# Count_3x7Seg_Display.net
KiCad netlist of a schematic drawn in Altium Designer
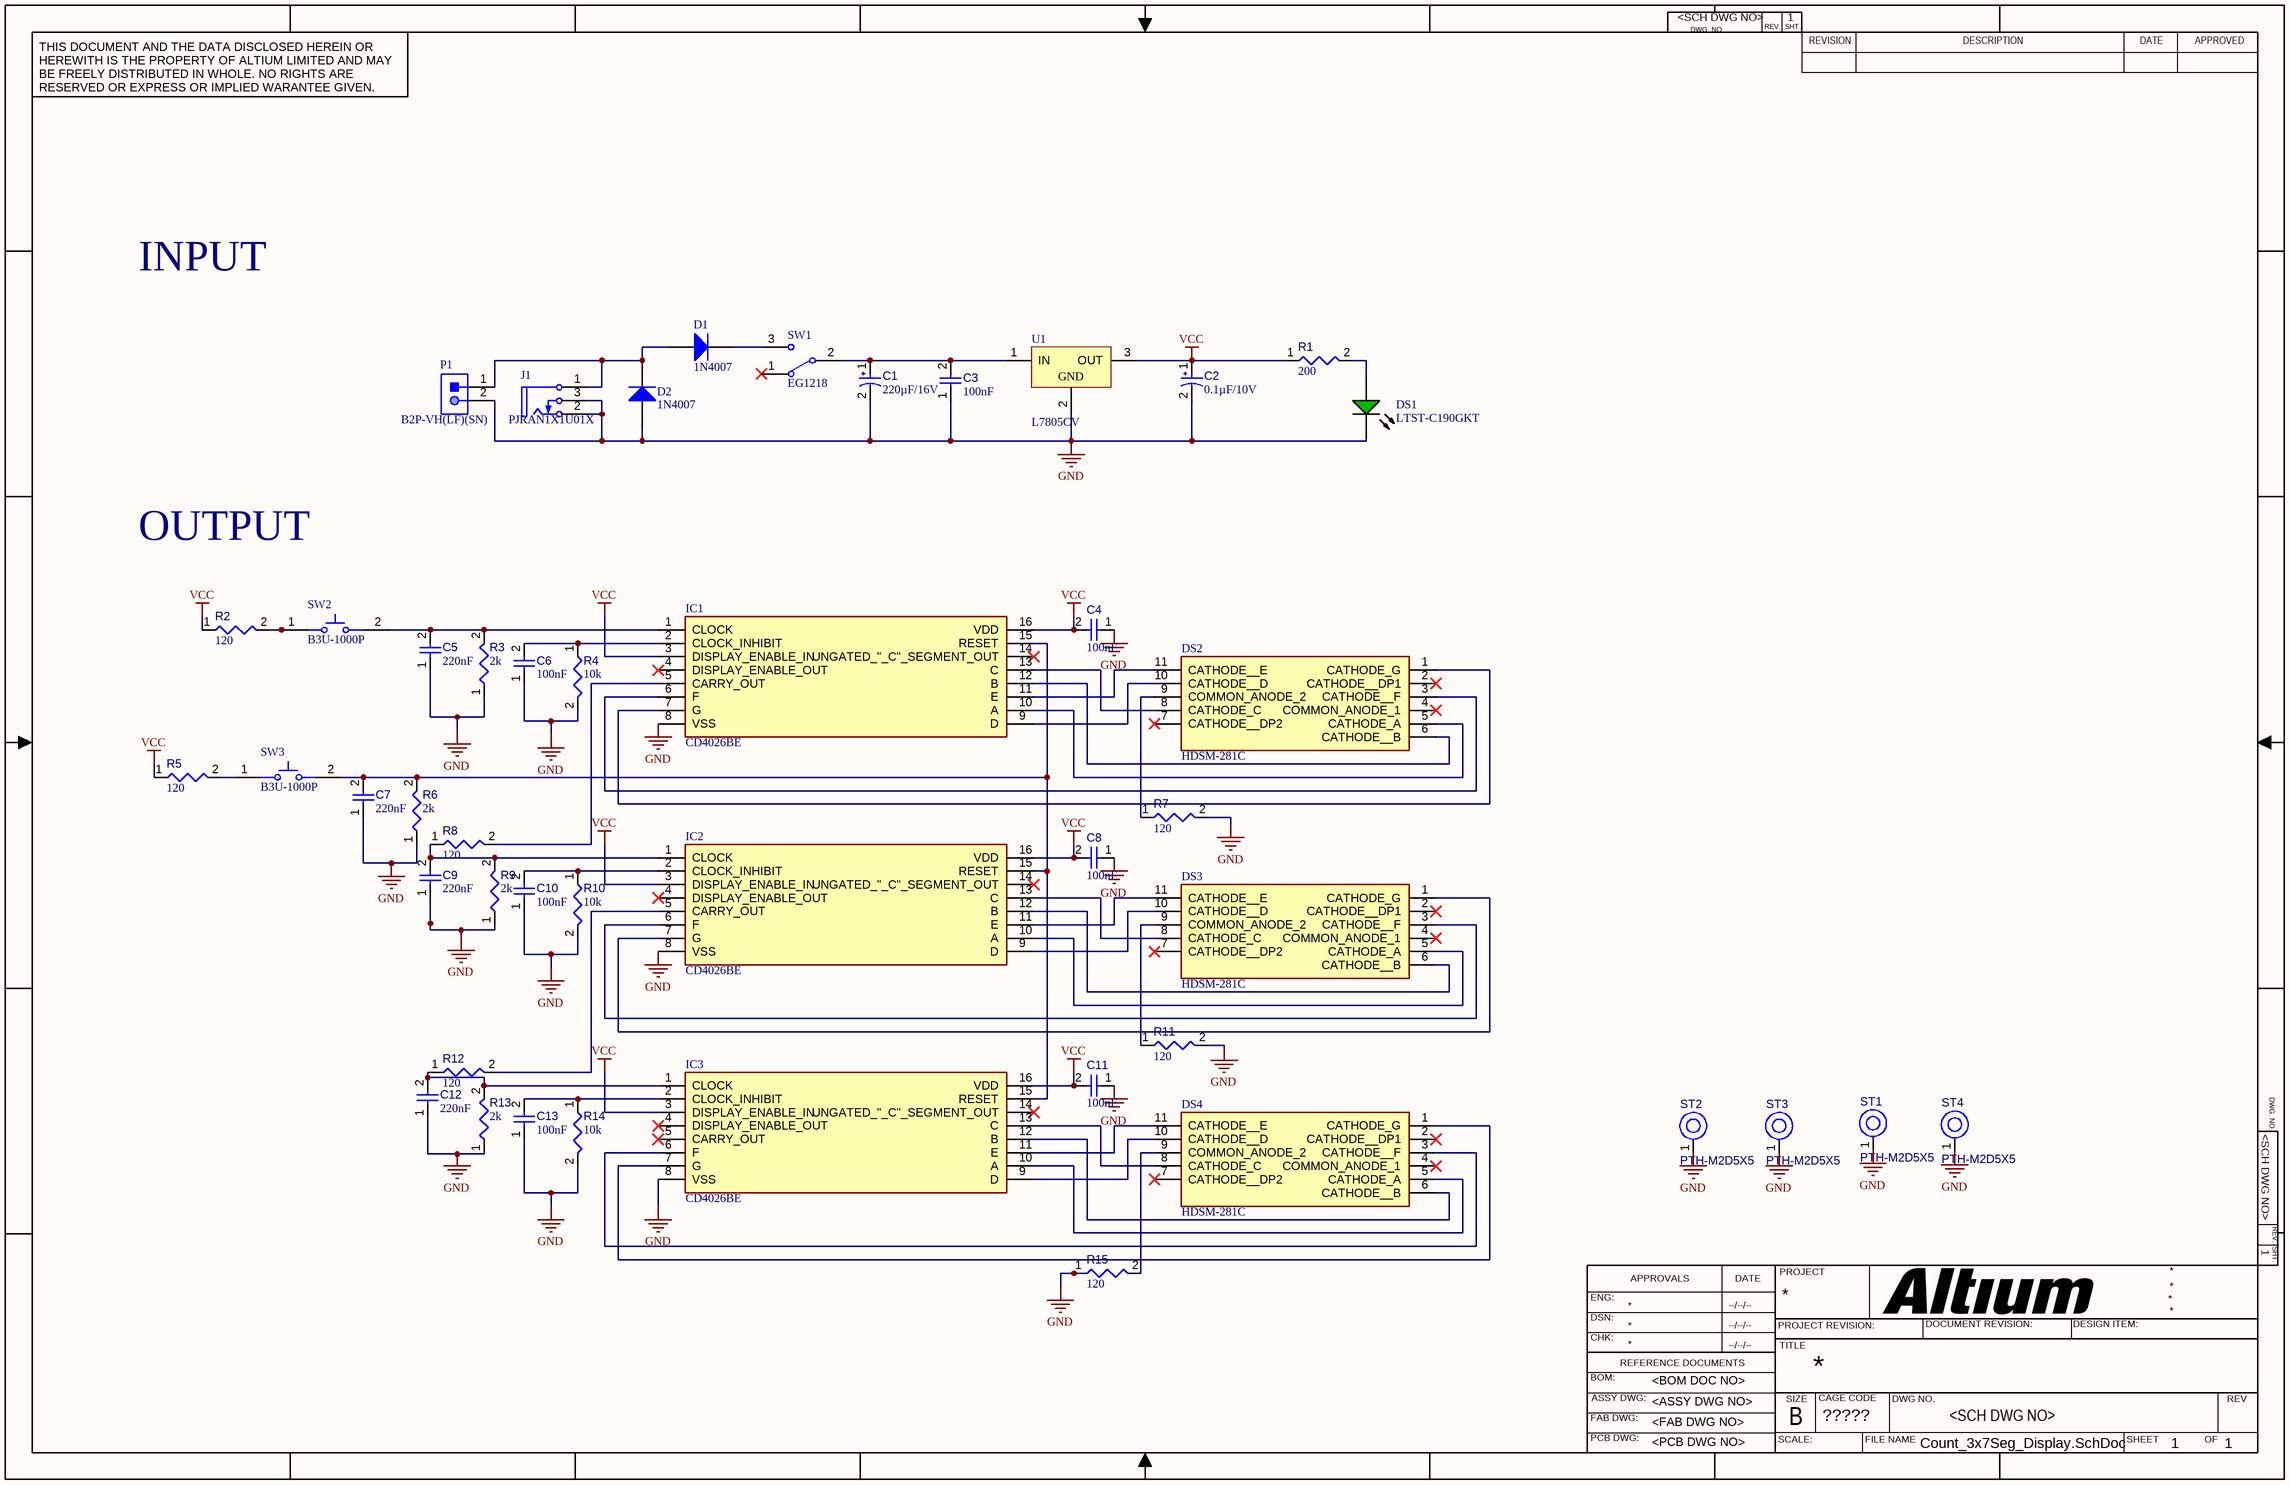
[diagram p0: Count_3x7Seg_Display.SchDoc]

(export (version "E")
  (design (tool "Eeschema 10.0.6"))
  (components
    (comp (ref "C1")
      (value "220µF/16V")
      (footprint "CAPPR55-250-1120X630X1220")
      (description "Aluminum Electrolytic Capacitor, 47 uF, +/-20%, 50 V, -40 to 85 degC, 2-Pin THD, RoHS, Bulk")
      (fields (field (name "TOLERANCE") "20%") (field (name "MANUFACTURER") "Panasonic"))
      (libsource (lib "Paris - Saclay University") (part "CAP-P-2"))
    )
    (comp (ref "C2")
      (value "0.1µF/10V")
      (footprint "CAPPR55-250-1120X630X1220")
      (description "Aluminum Electrolytic Capacitor, 47 uF, +/-20%, 50 V, -40 to 85 degC, 2-Pin THD, RoHS, Bulk")
      (fields (field (name "TOLERANCE") "20%") (field (name "MANUFACTURER") "Panasonic"))
      (libsource (lib "Paris - Saclay University") (part "CAP-P-2"))
    )
    (comp (ref "C3")
      (value "100nF")
      (footprint "CAPC1608X90X40NL10T20")
      (description "Chip Capacitor, 100 nF, +/- 10%, 50 V, 0603 (1608 Metric)")
      (fields (field (name "TOLERANCE") "10%") (field (name "Comment") "Capacitor 100 nF +/-10% 50 V 0603"))
      (libsource (lib "Paris - Saclay University") (part "CAP-NP-2"))
    )
    (comp (ref "C4")
      (value "100nF")
      (footprint "CAPC1608X90X40NL10T20")
      (description "Chip Capacitor, 100 nF, +/- 10%, 50 V, 0603 (1608 Metric)")
      (fields (field (name "TOLERANCE") "10%") (field (name "Comment") "Capacitor 100 nF +/-10% 50 V 0603"))
      (libsource (lib "Paris - Saclay University") (part "CAP-NP-2"))
    )
    (comp (ref "C5")
      (value "220nF")
      (footprint "CAPC0402(1005)60_L")
      (description "Chip Capacitor, 220nF +/-20%, 10V, 0402, Thickness 0.6 mm")
      (fields (field (name "TOLERANCE") "10%") (field (name "Comment") "Capacitor 220nF +/-20% 10V 0402"))
      (libsource (lib "Paris - Saclay University") (part "CAP-NP-2"))
    )
    (comp (ref "C6")
      (value "100nF")
      (footprint "CAPC1608X90X40NL10T20")
      (description "Chip Capacitor, 100 nF, +/- 10%, 50 V, 0603 (1608 Metric)")
      (fields (field (name "TOLERANCE") "10%") (field (name "Comment") "Capacitor 100 nF +/-10% 50 V 0603"))
      (libsource (lib "Paris - Saclay University") (part "CAP-NP-2"))
    )
    (comp (ref "C7")
      (value "220nF")
      (footprint "CAPC0402(1005)60_L")
      (description "Chip Capacitor, 220nF +/-20%, 10V, 0402, Thickness 0.6 mm")
      (fields (field (name "TOLERANCE") "10%") (field (name "Comment") "Capacitor 220nF +/-20% 10V 0402"))
      (libsource (lib "Paris - Saclay University") (part "CAP-NP-2"))
    )
    (comp (ref "C8")
      (value "100nF")
      (footprint "CAPC1608X90X40NL10T20")
      (description "Chip Capacitor, 100 nF, +/- 10%, 50 V, 0603 (1608 Metric)")
      (fields (field (name "TOLERANCE") "10%") (field (name "Comment") "Capacitor 100 nF +/-10% 50 V 0603"))
      (libsource (lib "Paris - Saclay University") (part "CAP-NP-2"))
    )
    (comp (ref "C9")
      (value "220nF")
      (footprint "CAPC0402(1005)60_L")
      (description "Chip Capacitor, 220nF +/-20%, 10V, 0402, Thickness 0.6 mm")
      (fields (field (name "TOLERANCE") "10%") (field (name "Comment") "Capacitor 220nF +/-20% 10V 0402"))
      (libsource (lib "Paris - Saclay University") (part "CAP-NP-2"))
    )
    (comp (ref "C10")
      (value "100nF")
      (footprint "CAPC1608X90X40NL10T20")
      (description "Chip Capacitor, 100 nF, +/- 10%, 50 V, 0603 (1608 Metric)")
      (fields (field (name "TOLERANCE") "10%") (field (name "Comment") "Capacitor 100 nF +/-10% 50 V 0603"))
      (libsource (lib "Paris - Saclay University") (part "CAP-NP-2"))
    )
    (comp (ref "C11")
      (value "100nF")
      (footprint "CAPC1608X90X40NL10T20")
      (description "Chip Capacitor, 100 nF, +/- 10%, 50 V, 0603 (1608 Metric)")
      (fields (field (name "TOLERANCE") "10%") (field (name "Comment") "Capacitor 100 nF +/-10% 50 V 0603"))
      (libsource (lib "Paris - Saclay University") (part "CAP-NP-2"))
    )
    (comp (ref "C12")
      (value "220nF")
      (footprint "CAPC0402(1005)60_L")
      (description "Chip Capacitor, 220nF +/-20%, 10V, 0402, Thickness 0.6 mm")
      (fields (field (name "TOLERANCE") "10%") (field (name "Comment") "Capacitor 220nF +/-20% 10V 0402"))
      (libsource (lib "Paris - Saclay University") (part "CAP-NP-2"))
    )
    (comp (ref "C13")
      (value "100nF")
      (footprint "CAPC1608X90X40NL10T20")
      (description "Chip Capacitor, 100 nF, +/- 10%, 50 V, 0603 (1608 Metric)")
      (fields (field (name "TOLERANCE") "10%") (field (name "Comment") "Capacitor 100 nF +/-10% 50 V 0603"))
      (libsource (lib "Paris - Saclay University") (part "CAP-NP-2"))
    )
    (comp (ref "D1")
      (value "1N4007")
      (footprint "FAIR-DO-41-2")
      (description "General Purpose Rectifier, 1.1 V, 1.0 A, -55 to 175 degC, 2-Pin DO-41, RoHS, Tape and Reel")
      (fields (field (name "MANUFACTURER") "Fairchild"))
      (libsource (lib "Paris - Saclay University") (part "KESE-D_K1A2-2"))
    )
    (comp (ref "D2")
      (value "1N4007")
      (footprint "FAIR-DO-41-2")
      (description "General Purpose Rectifier, 1.1 V, 1.0 A, -55 to 175 degC, 2-Pin DO-41, RoHS, Tape and Reel")
      (fields (field (name "MANUFACTURER") "Fairchild"))
      (libsource (lib "Paris - Saclay University") (part "KESE-D_K1A2-2"))
    )
    (comp (ref "DS1")
      (value "LTST-C190GKT")
      (footprint "LTST-C190GKT_V")
      (description "LED Uni-Color Green, 100 mW, 30 mA, -55 to 85 degC, 2-Pin SMD, RoHS, Tape and Reel")
      (fields (field (name "POWER") "100mW") (field (name "MANUFACTURER") "Lite-On"))
      (libsource (lib "Paris - Saclay University") (part "LED-GREEN-AK-2"))
    )
    (comp (ref "DS2")
      (value "HDSM-281C")
      (footprint "SamacSys:HDSM283L")
      (description "Display")
      (fields (field (name "MOUSER PART NUMBER") "630-HDSM-281C"))
      (libsource (lib "*") (part "HDSM-281C"))
    )
    (comp (ref "DS3")
      (value "HDSM-281C")
      (footprint "SamacSys:HDSM283L")
      (description "Display")
      (fields (field (name "MOUSER PART NUMBER") "630-HDSM-281C"))
      (libsource (lib "*") (part "HDSM-281C"))
    )
    (comp (ref "DS4")
      (value "HDSM-281C")
      (footprint "SamacSys:HDSM283L")
      (description "Display")
      (fields (field (name "MOUSER PART NUMBER") "630-HDSM-281C"))
      (libsource (lib "*") (part "HDSM-281C"))
    )
    (comp (ref "IC1")
      (value "CD4026BE")
      (footprint "SamacSys:DIP794W53P254L1930H508Q16N")
      (description "Integrated Circuit")
      (fields (field (name "MOUSER PART NUMBER") "595-CD4026BE"))
      (libsource (lib "*") (part "CD4026BE"))
    )
    (comp (ref "IC2")
      (value "CD4026BE")
      (footprint "SamacSys:DIP794W53P254L1930H508Q16N")
      (description "Integrated Circuit")
      (fields (field (name "MOUSER PART NUMBER") "595-CD4026BE"))
      (libsource (lib "*") (part "CD4026BE"))
    )
    (comp (ref "IC3")
      (value "CD4026BE")
      (footprint "SamacSys:DIP794W53P254L1930H508Q16N")
      (description "Integrated Circuit")
      (fields (field (name "MOUSER PART NUMBER") "595-CD4026BE"))
      (libsource (lib "*") (part "CD4026BE"))
    )
    (comp (ref "J1")
      (value "PJRAN1X1U01X")
      (footprint "SWIT-PJRAN1X1U01X_V")
      (description "Female Phono Jack, 3 Position, Height 13 mm, Tail Length 4 mm, RoHS, Bulk")
      (fields (field (name "MANUFACTURER") "Switchcraft"))
      (libsource (lib "Paris - Saclay University") (part "JACK-2CD3-TN"))
    )
    (comp (ref "P1")
      (value "B2P-VH(LF)(SN)")
      (footprint "JST-B2P-VH(LF)(SN)_V")
      (fields (field (name "MANUFACTURER") "JST"))
      (libsource (lib "Paris - Saclay University") (part "CN-1P-M-R2"))
    )
    (comp (ref "R1")
      (value "200")
      (footprint "RESC0402(1005)_L")
      (description "200R 0.063W 5% 0402 (1005 Metric)  SMD")
      (fields (field (name "TOLERANCE") "5%") (field (name "POWER") "63mW"))
      (libsource (lib "Paris - Saclay University") (part "200R2J"))
    )
    (comp (ref "R2")
      (value "120")
      (footprint "RESC0603(1608)_L")
      (description "120R 0.1W 5% 0603 (1608 Metric)  SMD")
      (fields (field (name "POWER") "100mW") (field (name "TOLERANCE") "5%"))
      (libsource (lib "Paris - Saclay University") (part "120R3J"))
    )
    (comp (ref "R3")
      (value "2k")
      (footprint "RESC0402(1005)_L")
      (description "Chip Resistor, 2 kOhms, +/-5 %, 63 mW, -55 to 155 degC, 0402")
      (fields (field (name "TOLERANCE") "5%") (field (name "POWER") "63mW"))
      (libsource (lib "Paris - Saclay University") (part "RES-2"))
    )
    (comp (ref "R4")
      (value "10k")
      (footprint "RESC1005X40X25ML05T05")
      (description "Chip Resistor, 10 KOhm, +/- 1%, 0.1 W, -55 to 155 degC, 0402 (1005 Metric)")
      (fields (field (name "TOLERANCE") "1%") (field (name "POWER") "100mW"))
      (libsource (lib "Paris - Saclay University") (part "RES-2"))
    )
    (comp (ref "R5")
      (value "120")
      (footprint "RESC0603(1608)_L")
      (description "120R 0.1W 5% 0603 (1608 Metric)  SMD")
      (fields (field (name "POWER") "100mW") (field (name "TOLERANCE") "5%"))
      (libsource (lib "Paris - Saclay University") (part "120R3J"))
    )
    (comp (ref "R6")
      (value "2k")
      (footprint "RESC0402(1005)_L")
      (description "Chip Resistor, 2 kOhms, +/-5 %, 63 mW, -55 to 155 degC, 0402")
      (fields (field (name "TOLERANCE") "5%") (field (name "POWER") "63mW"))
      (libsource (lib "Paris - Saclay University") (part "RES-2"))
    )
    (comp (ref "R7")
      (value "120")
      (footprint "RESC0603(1608)_L")
      (description "120R 0.1W 5% 0603 (1608 Metric)  SMD")
      (fields (field (name "POWER") "100mW") (field (name "TOLERANCE") "5%"))
      (libsource (lib "Paris - Saclay University") (part "120R3J"))
    )
    (comp (ref "R8")
      (value "120")
      (footprint "RESC0603(1608)_L")
      (description "120R 0.1W 5% 0603 (1608 Metric)  SMD")
      (fields (field (name "POWER") "100mW") (field (name "TOLERANCE") "5%"))
      (libsource (lib "Paris - Saclay University") (part "120R3J"))
    )
    (comp (ref "R9")
      (value "2k")
      (footprint "RESC0402(1005)_L")
      (description "Chip Resistor, 2 kOhms, +/-5 %, 63 mW, -55 to 155 degC, 0402")
      (fields (field (name "TOLERANCE") "5%") (field (name "POWER") "63mW"))
      (libsource (lib "Paris - Saclay University") (part "RES-2"))
    )
    (comp (ref "R10")
      (value "10k")
      (footprint "RESC1005X40X25ML05T05")
      (description "Chip Resistor, 10 KOhm, +/- 1%, 0.1 W, -55 to 155 degC, 0402 (1005 Metric)")
      (fields (field (name "TOLERANCE") "1%") (field (name "POWER") "100mW"))
      (libsource (lib "Paris - Saclay University") (part "RES-2"))
    )
    (comp (ref "R11")
      (value "120")
      (footprint "RESC0603(1608)_L")
      (description "120R 0.1W 5% 0603 (1608 Metric)  SMD")
      (fields (field (name "POWER") "100mW") (field (name "TOLERANCE") "5%"))
      (libsource (lib "Paris - Saclay University") (part "120R3J"))
    )
    (comp (ref "R12")
      (value "120")
      (footprint "RESC0603(1608)_L")
      (description "120R 0.1W 5% 0603 (1608 Metric)  SMD")
      (fields (field (name "POWER") "100mW") (field (name "TOLERANCE") "5%"))
      (libsource (lib "Paris - Saclay University") (part "120R3J"))
    )
    (comp (ref "R13")
      (value "2k")
      (footprint "RESC0402(1005)_L")
      (description "Chip Resistor, 2 kOhms, +/-5 %, 63 mW, -55 to 155 degC, 0402")
      (fields (field (name "TOLERANCE") "5%") (field (name "POWER") "63mW"))
      (libsource (lib "Paris - Saclay University") (part "RES-2"))
    )
    (comp (ref "R14")
      (value "10k")
      (footprint "RESC1005X40X25ML05T05")
      (description "Chip Resistor, 10 KOhm, +/- 1%, 0.1 W, -55 to 155 degC, 0402 (1005 Metric)")
      (fields (field (name "TOLERANCE") "1%") (field (name "POWER") "100mW"))
      (libsource (lib "Paris - Saclay University") (part "RES-2"))
    )
    (comp (ref "R15")
      (value "120")
      (footprint "RESC0603(1608)_L")
      (description "120R 0.1W 5% 0603 (1608 Metric)  SMD")
      (fields (field (name "POWER") "100mW") (field (name "TOLERANCE") "5%"))
      (libsource (lib "Paris - Saclay University") (part "120R3J"))
    )
    (comp (ref "ST1")
      (value "PTH-M2D5X5")
      (footprint "PTH-M2D5X5")
      (description "M2 PTH (2.5mm), 5mm pad")
      (libsource (lib "Paris - Saclay University") (part "CMP-00028-00000-1"))
    )
    (comp (ref "ST2")
      (value "PTH-M2D5X5")
      (footprint "PTH-M2D5X5")
      (description "M2 PTH (2.5mm), 5mm pad")
      (libsource (lib "Paris - Saclay University") (part "CMP-00028-00000-1"))
    )
    (comp (ref "ST3")
      (value "PTH-M2D5X5")
      (footprint "PTH-M2D5X5")
      (description "M2 PTH (2.5mm), 5mm pad")
      (libsource (lib "Paris - Saclay University") (part "CMP-00028-00000-1"))
    )
    (comp (ref "ST4")
      (value "PTH-M2D5X5")
      (footprint "PTH-M2D5X5")
      (description "M2 PTH (2.5mm), 5mm pad")
      (libsource (lib "Paris - Saclay University") (part "CMP-00028-00000-1"))
    )
    (comp (ref "SW1")
      (value "EG1218")
      (footprint "ESWI-EG1218_V")
      (description "Slide Switch, SPDT, 500 V, -20 to 70 degC, 3-Pin THD, RoHS, Bulk")
      (fields (field (name "MANUFACTURER") "E-Switch"))
      (libsource (lib "Paris - Saclay University") (part "SW-SPDT-3_B"))
    )
    (comp (ref "SW2")
      (value "B3U-1000P")
      (footprint "OMRON-B3U-1000_V")
      (description "Tactile Switch, SPST-NO, 0.05 A, 12 V, -25 to 70 degC, 2-Pin SMD, RoHS, Tape and Reel")
      (fields (field (name "MANUFACTURER") "Omron Electronic Components"))
      (libsource (lib "Paris - Saclay University") (part "SW-SPST-NO-2"))
    )
    (comp (ref "SW3")
      (value "B3U-1000P")
      (footprint "OMRON-B3U-1000_V")
      (description "Tactile Switch, SPST-NO, 0.05 A, 12 V, -25 to 70 degC, 2-Pin SMD, RoHS, Tape and Reel")
      (fields (field (name "MANUFACTURER") "Omron Electronic Components"))
      (libsource (lib "Paris - Saclay University") (part "SW-SPST-NO-2"))
    )
    (comp (ref "U1")
      (value "L7805CV")
      (footprint "TO220")
      (description "Positive Voltage Regulator IC, 1.5 A, 5 V, 0 to 125 degC, 3-Pin TO-220, RoHS, Tube")
      (fields (field (name "MANUFACTURER") "STMicroelectronics"))
      (libsource (lib "Paris - Saclay University") (part "PM-REG-L4940-SIL3"))
    )
  )
  (nets
    (net (code "1") (name "GND") (class "Default")
      (node (ref "C1") (pin "2") (pinfunction "2_2") (pintype "passive"))
      (node (ref "C10") (pin "1") (pinfunction "1_1") (pintype "passive"))
      (node (ref "C11") (pin "1") (pinfunction "1_1") (pintype "passive"))
      (node (ref "C12") (pin "1") (pinfunction "1_1") (pintype "passive"))
      (node (ref "C13") (pin "1") (pinfunction "1_1") (pintype "passive"))
      (node (ref "C2") (pin "2") (pinfunction "2_2") (pintype "passive"))
      (node (ref "C3") (pin "1") (pinfunction "1_1") (pintype "passive"))
      (node (ref "C4") (pin "1") (pinfunction "1_1") (pintype "passive"))
      (node (ref "C5") (pin "1") (pinfunction "1_1") (pintype "passive"))
      (node (ref "C6") (pin "1") (pinfunction "1_1") (pintype "passive"))
      (node (ref "C7") (pin "1") (pinfunction "1_1") (pintype "passive"))
      (node (ref "C8") (pin "1") (pinfunction "1_1") (pintype "passive"))
      (node (ref "C9") (pin "1") (pinfunction "1_1") (pintype "passive"))
      (node (ref "D2") (pin "2") (pinfunction "A_2") (pintype "passive"))
      (node (ref "DS1") (pin "2") (pinfunction "K_2") (pintype "passive"))
      (node (ref "IC1") (pin "8") (pinfunction "VSS_8") (pintype "passive"))
      (node (ref "IC2") (pin "8") (pinfunction "VSS_8") (pintype "passive"))
      (node (ref "IC3") (pin "8") (pinfunction "VSS_8") (pintype "passive"))
      (node (ref "J1") (pin "2") (pinfunction "TIP_2") (pintype "passive"))
      (node (ref "J1") (pin "3") (pinfunction "SHUNT_3") (pintype "passive"))
      (node (ref "P1") (pin "2") (pinfunction "2_2") (pintype "passive"))
      (node (ref "R10") (pin "2") (pinfunction "2_2") (pintype "passive"))
      (node (ref "R11") (pin "2") (pinfunction "2_2") (pintype "passive"))
      (node (ref "R13") (pin "1") (pinfunction "1_1") (pintype "passive"))
      (node (ref "R14") (pin "2") (pinfunction "2_2") (pintype "passive"))
      (node (ref "R15") (pin "1") (pinfunction "1_1") (pintype "passive"))
      (node (ref "R3") (pin "1") (pinfunction "1_1") (pintype "passive"))
      (node (ref "R4") (pin "2") (pinfunction "2_2") (pintype "passive"))
      (node (ref "R6") (pin "1") (pinfunction "1_1") (pintype "passive"))
      (node (ref "R7") (pin "2") (pinfunction "2_2") (pintype "passive"))
      (node (ref "R9") (pin "1") (pinfunction "1_1") (pintype "passive"))
      (node (ref "ST1") (pin "1") (pinfunction "H1_1") (pintype "passive"))
      (node (ref "ST2") (pin "1") (pinfunction "H1_1") (pintype "passive"))
      (node (ref "ST3") (pin "1") (pinfunction "H1_1") (pintype "passive"))
      (node (ref "ST4") (pin "1") (pinfunction "H1_1") (pintype "passive"))
      (node (ref "U1") (pin "2") (pinfunction "GND_2") (pintype "power_in"))
    )
    (net (code "2") (name "Net-(D1-A)") (class "Default")
      (node (ref "D1") (pin "2") (pinfunction "A_2") (pintype "passive"))
      (node (ref "D2") (pin "1") (pinfunction "K_1") (pintype "passive"))
      (node (ref "J1") (pin "1") (pinfunction "SLEEVE_1") (pintype "passive"))
      (node (ref "P1") (pin "1") (pinfunction "1_1") (pintype "passive"))
    )
    (net (code "3") (name "Net-(D1-K)") (class "Default")
      (node (ref "D1") (pin "1") (pinfunction "K_1") (pintype "passive"))
      (node (ref "SW1") (pin "3") (pinfunction "3_3") (pintype "passive"))
    )
    (net (code "4") (name "Net-(DS1-A)") (class "Default")
      (node (ref "DS1") (pin "1") (pinfunction "A_1") (pintype "passive"))
      (node (ref "R1") (pin "2") (pinfunction "2_2") (pintype "passive"))
    )
    (net (code "5") (name "Net-(DS2-CATHODE_A)") (class "Default")
      (node (ref "DS2") (pin "5") (pinfunction "CATHODE_A_5") (pintype "passive"))
      (node (ref "IC1") (pin "10") (pinfunction "A_10") (pintype "passive"))
    )
    (net (code "6") (name "Net-(DS2-CATHODE_C)") (class "Default")
      (node (ref "DS2") (pin "8") (pinfunction "CATHODE_C_8") (pintype "passive"))
      (node (ref "IC1") (pin "13") (pinfunction "C_13") (pintype "passive"))
    )
    (net (code "7") (name "Net-(DS2-CATHODE_G)") (class "Default")
      (node (ref "DS2") (pin "1") (pinfunction "CATHODE_G_1") (pintype "passive"))
      (node (ref "IC1") (pin "7") (pinfunction "G_7") (pintype "passive"))
    )
    (net (code "8") (name "Net-(DS2-CATHODE__B)") (class "Default")
      (node (ref "DS2") (pin "6") (pinfunction "CATHODE__B_6") (pintype "passive"))
      (node (ref "IC1") (pin "12") (pinfunction "B_12") (pintype "passive"))
    )
    (net (code "9") (name "Net-(DS2-CATHODE__D)") (class "Default")
      (node (ref "DS2") (pin "10") (pinfunction "CATHODE__D_10") (pintype "passive"))
      (node (ref "IC1") (pin "9") (pinfunction "D_9") (pintype "passive"))
    )
    (net (code "10") (name "Net-(DS2-CATHODE__E)") (class "Default")
      (node (ref "DS2") (pin "11") (pinfunction "CATHODE__E_11") (pintype "passive"))
      (node (ref "IC1") (pin "11") (pinfunction "E_11") (pintype "passive"))
    )
    (net (code "11") (name "Net-(DS2-CATHODE__F)") (class "Default")
      (node (ref "DS2") (pin "3") (pinfunction "CATHODE__F_3") (pintype "passive"))
      (node (ref "IC1") (pin "6") (pinfunction "F_6") (pintype "passive"))
    )
    (net (code "12") (name "Net-(DS2-COMMON_ANODE_2)") (class "Default")
      (node (ref "DS2") (pin "9") (pinfunction "COMMON_ANODE_2_9") (pintype "passive"))
      (node (ref "R7") (pin "1") (pinfunction "1_1") (pintype "passive"))
    )
    (net (code "13") (name "Net-(DS3-CATHODE_A)") (class "Default")
      (node (ref "DS3") (pin "5") (pinfunction "CATHODE_A_5") (pintype "passive"))
      (node (ref "IC2") (pin "10") (pinfunction "A_10") (pintype "passive"))
    )
    (net (code "14") (name "Net-(DS3-CATHODE_C)") (class "Default")
      (node (ref "DS3") (pin "8") (pinfunction "CATHODE_C_8") (pintype "passive"))
      (node (ref "IC2") (pin "13") (pinfunction "C_13") (pintype "passive"))
    )
    (net (code "15") (name "Net-(DS3-CATHODE_G)") (class "Default")
      (node (ref "DS3") (pin "1") (pinfunction "CATHODE_G_1") (pintype "passive"))
      (node (ref "IC2") (pin "7") (pinfunction "G_7") (pintype "passive"))
    )
    (net (code "16") (name "Net-(DS3-CATHODE__B)") (class "Default")
      (node (ref "DS3") (pin "6") (pinfunction "CATHODE__B_6") (pintype "passive"))
      (node (ref "IC2") (pin "12") (pinfunction "B_12") (pintype "passive"))
    )
    (net (code "17") (name "Net-(DS3-CATHODE__D)") (class "Default")
      (node (ref "DS3") (pin "10") (pinfunction "CATHODE__D_10") (pintype "passive"))
      (node (ref "IC2") (pin "9") (pinfunction "D_9") (pintype "passive"))
    )
    (net (code "18") (name "Net-(DS3-CATHODE__E)") (class "Default")
      (node (ref "DS3") (pin "11") (pinfunction "CATHODE__E_11") (pintype "passive"))
      (node (ref "IC2") (pin "11") (pinfunction "E_11") (pintype "passive"))
    )
    (net (code "19") (name "Net-(DS3-CATHODE__F)") (class "Default")
      (node (ref "DS3") (pin "3") (pinfunction "CATHODE__F_3") (pintype "passive"))
      (node (ref "IC2") (pin "6") (pinfunction "F_6") (pintype "passive"))
    )
    (net (code "20") (name "Net-(DS3-COMMON_ANODE_2)") (class "Default")
      (node (ref "DS3") (pin "9") (pinfunction "COMMON_ANODE_2_9") (pintype "passive"))
      (node (ref "R11") (pin "1") (pinfunction "1_1") (pintype "passive"))
    )
    (net (code "21") (name "Net-(DS4-CATHODE_A)") (class "Default")
      (node (ref "DS4") (pin "5") (pinfunction "CATHODE_A_5") (pintype "passive"))
      (node (ref "IC3") (pin "10") (pinfunction "A_10") (pintype "passive"))
    )
    (net (code "22") (name "Net-(DS4-CATHODE_C)") (class "Default")
      (node (ref "DS4") (pin "8") (pinfunction "CATHODE_C_8") (pintype "passive"))
      (node (ref "IC3") (pin "13") (pinfunction "C_13") (pintype "passive"))
    )
    (net (code "23") (name "Net-(DS4-CATHODE_G)") (class "Default")
      (node (ref "DS4") (pin "1") (pinfunction "CATHODE_G_1") (pintype "passive"))
      (node (ref "IC3") (pin "7") (pinfunction "G_7") (pintype "passive"))
    )
    (net (code "24") (name "Net-(DS4-CATHODE__B)") (class "Default")
      (node (ref "DS4") (pin "6") (pinfunction "CATHODE__B_6") (pintype "passive"))
      (node (ref "IC3") (pin "12") (pinfunction "B_12") (pintype "passive"))
    )
    (net (code "25") (name "Net-(DS4-CATHODE__D)") (class "Default")
      (node (ref "DS4") (pin "10") (pinfunction "CATHODE__D_10") (pintype "passive"))
      (node (ref "IC3") (pin "9") (pinfunction "D_9") (pintype "passive"))
    )
    (net (code "26") (name "Net-(DS4-CATHODE__E)") (class "Default")
      (node (ref "DS4") (pin "11") (pinfunction "CATHODE__E_11") (pintype "passive"))
      (node (ref "IC3") (pin "11") (pinfunction "E_11") (pintype "passive"))
    )
    (net (code "27") (name "Net-(DS4-CATHODE__F)") (class "Default")
      (node (ref "DS4") (pin "3") (pinfunction "CATHODE__F_3") (pintype "passive"))
      (node (ref "IC3") (pin "6") (pinfunction "F_6") (pintype "passive"))
    )
    (net (code "28") (name "Net-(DS4-COMMON_ANODE_2)") (class "Default")
      (node (ref "DS4") (pin "9") (pinfunction "COMMON_ANODE_2_9") (pintype "passive"))
      (node (ref "R15") (pin "2") (pinfunction "2_2") (pintype "passive"))
    )
    (net (code "29") (name "Net-(IC1-CARRY_OUT)") (class "Default")
      (node (ref "IC1") (pin "5") (pinfunction "CARRY_OUT_5") (pintype "passive"))
      (node (ref "R8") (pin "2") (pinfunction "2_2") (pintype "passive"))
    )
    (net (code "30") (name "Net-(IC1-CLOCK)") (class "Default")
      (node (ref "C5") (pin "2") (pinfunction "2_2") (pintype "passive"))
      (node (ref "IC1") (pin "1") (pinfunction "CLOCK_1") (pintype "passive"))
      (node (ref "R3") (pin "2") (pinfunction "2_2") (pintype "passive"))
      (node (ref "SW2") (pin "2") (pinfunction "2_2") (pintype "passive"))
    )
    (net (code "31") (name "Net-(IC1-CLOCK_INHIBIT)") (class "Default")
      (node (ref "C6") (pin "2") (pinfunction "2_2") (pintype "passive"))
      (node (ref "IC1") (pin "2") (pinfunction "CLOCK_INHIBIT_2") (pintype "passive"))
      (node (ref "R4") (pin "1") (pinfunction "1_1") (pintype "passive"))
    )
    (net (code "32") (name "Net-(IC1-RESET)") (class "Default")
      (node (ref "C7") (pin "2") (pinfunction "2_2") (pintype "passive"))
      (node (ref "IC1") (pin "15") (pinfunction "RESET_15") (pintype "passive"))
      (node (ref "IC2") (pin "15") (pinfunction "RESET_15") (pintype "passive"))
      (node (ref "IC3") (pin "15") (pinfunction "RESET_15") (pintype "passive"))
      (node (ref "R6") (pin "2") (pinfunction "2_2") (pintype "passive"))
      (node (ref "SW3") (pin "2") (pinfunction "2_2") (pintype "passive"))
    )
    (net (code "33") (name "Net-(IC2-CARRY_OUT)") (class "Default")
      (node (ref "IC2") (pin "5") (pinfunction "CARRY_OUT_5") (pintype "passive"))
      (node (ref "R12") (pin "2") (pinfunction "2_2") (pintype "passive"))
    )
    (net (code "34") (name "Net-(IC2-CLOCK)") (class "Default")
      (node (ref "C9") (pin "2") (pinfunction "2_2") (pintype "passive"))
      (node (ref "IC2") (pin "1") (pinfunction "CLOCK_1") (pintype "passive"))
      (node (ref "R8") (pin "1") (pinfunction "1_1") (pintype "passive"))
      (node (ref "R9") (pin "2") (pinfunction "2_2") (pintype "passive"))
    )
    (net (code "35") (name "Net-(IC2-CLOCK_INHIBIT)") (class "Default")
      (node (ref "C10") (pin "2") (pinfunction "2_2") (pintype "passive"))
      (node (ref "IC2") (pin "2") (pinfunction "CLOCK_INHIBIT_2") (pintype "passive"))
      (node (ref "R10") (pin "1") (pinfunction "1_1") (pintype "passive"))
    )
    (net (code "36") (name "Net-(IC3-CLOCK)") (class "Default")
      (node (ref "C12") (pin "2") (pinfunction "2_2") (pintype "passive"))
      (node (ref "IC3") (pin "1") (pinfunction "CLOCK_1") (pintype "passive"))
      (node (ref "R12") (pin "1") (pinfunction "1_1") (pintype "passive"))
      (node (ref "R13") (pin "2") (pinfunction "2_2") (pintype "passive"))
    )
    (net (code "37") (name "Net-(IC3-CLOCK_INHIBIT)") (class "Default")
      (node (ref "C13") (pin "2") (pinfunction "2_2") (pintype "passive"))
      (node (ref "IC3") (pin "2") (pinfunction "CLOCK_INHIBIT_2") (pintype "passive"))
      (node (ref "R14") (pin "1") (pinfunction "1_1") (pintype "passive"))
    )
    (net (code "38") (name "Net-(R2-Pad2)") (class "Default")
      (node (ref "R2") (pin "2") (pinfunction "2_2") (pintype "passive"))
      (node (ref "SW2") (pin "1") (pinfunction "1_1") (pintype "passive"))
    )
    (net (code "39") (name "Net-(R5-Pad2)") (class "Default")
      (node (ref "R5") (pin "2") (pinfunction "2_2") (pintype "passive"))
      (node (ref "SW3") (pin "1") (pinfunction "1_1") (pintype "passive"))
    )
    (net (code "40") (name "Net-(SW1-COM)") (class "Default")
      (node (ref "C1") (pin "1") (pinfunction "1_1") (pintype "passive"))
      (node (ref "C3") (pin "2") (pinfunction "2_2") (pintype "passive"))
      (node (ref "SW1") (pin "2") (pinfunction "COM_2") (pintype "passive"))
      (node (ref "U1") (pin "1") (pinfunction "IN_1") (pintype "power_in"))
    )
    (net (code "41") (name "VCC") (class "Default")
      (node (ref "C11") (pin "2") (pinfunction "2_2") (pintype "passive"))
      (node (ref "C2") (pin "1") (pinfunction "1_1") (pintype "passive"))
      (node (ref "C4") (pin "2") (pinfunction "2_2") (pintype "passive"))
      (node (ref "C8") (pin "2") (pinfunction "2_2") (pintype "passive"))
      (node (ref "IC1") (pin "16") (pinfunction "VDD_16") (pintype "passive"))
      (node (ref "IC1") (pin "3") (pinfunction "DISPLAY_ENABLE_IN_3") (pintype "passive"))
      (node (ref "IC2") (pin "16") (pinfunction "VDD_16") (pintype "passive"))
      (node (ref "IC2") (pin "3") (pinfunction "DISPLAY_ENABLE_IN_3") (pintype "passive"))
      (node (ref "IC3") (pin "16") (pinfunction "VDD_16") (pintype "passive"))
      (node (ref "IC3") (pin "3") (pinfunction "DISPLAY_ENABLE_IN_3") (pintype "passive"))
      (node (ref "R1") (pin "1") (pinfunction "1_1") (pintype "passive"))
      (node (ref "R2") (pin "1") (pinfunction "1_1") (pintype "passive"))
      (node (ref "R5") (pin "1") (pinfunction "1_1") (pintype "passive"))
      (node (ref "U1") (pin "3") (pinfunction "OUT_3") (pintype "power_in"))
    )
    (net (code "42") (name "unconnected-(DS2-CATHODE__DP1-Pad2)") (class "Default")
      (node (ref "DS2") (pin "2") (pinfunction "CATHODE__DP1_2") (pintype "passive+no_connect"))
    )
    (net (code "43") (name "unconnected-(DS2-CATHODE__DP2-Pad7)") (class "Default")
      (node (ref "DS2") (pin "7") (pinfunction "CATHODE__DP2_7") (pintype "passive+no_connect"))
    )
    (net (code "44") (name "unconnected-(DS2-COMMON_ANODE_1-Pad4)") (class "Default")
      (node (ref "DS2") (pin "4") (pinfunction "COMMON_ANODE_1_4") (pintype "passive+no_connect"))
    )
    (net (code "45") (name "unconnected-(DS3-CATHODE__DP1-Pad2)") (class "Default")
      (node (ref "DS3") (pin "2") (pinfunction "CATHODE__DP1_2") (pintype "passive+no_connect"))
    )
    (net (code "46") (name "unconnected-(DS3-CATHODE__DP2-Pad7)") (class "Default")
      (node (ref "DS3") (pin "7") (pinfunction "CATHODE__DP2_7") (pintype "passive+no_connect"))
    )
    (net (code "47") (name "unconnected-(DS3-COMMON_ANODE_1-Pad4)") (class "Default")
      (node (ref "DS3") (pin "4") (pinfunction "COMMON_ANODE_1_4") (pintype "passive+no_connect"))
    )
    (net (code "48") (name "unconnected-(DS4-CATHODE__DP1-Pad2)") (class "Default")
      (node (ref "DS4") (pin "2") (pinfunction "CATHODE__DP1_2") (pintype "passive+no_connect"))
    )
    (net (code "49") (name "unconnected-(DS4-CATHODE__DP2-Pad7)") (class "Default")
      (node (ref "DS4") (pin "7") (pinfunction "CATHODE__DP2_7") (pintype "passive+no_connect"))
    )
    (net (code "50") (name "unconnected-(DS4-COMMON_ANODE_1-Pad4)") (class "Default")
      (node (ref "DS4") (pin "4") (pinfunction "COMMON_ANODE_1_4") (pintype "passive+no_connect"))
    )
    (net (code "51") (name "unconnected-(IC1-DISPLAY_ENABLE_OUT-Pad4)") (class "Default")
      (node (ref "IC1") (pin "4") (pinfunction "DISPLAY_ENABLE_OUT_4") (pintype "passive+no_connect"))
    )
    (net (code "52") (name "unconnected-(IC1-UNGATED_\"_C\"_SEGMENT_OUT-Pad14)") (class "Default")
      (node (ref "IC1") (pin "14") (pinfunction "UNGATED_\"_C\"_SEGMENT_OUT_14") (pintype "passive+no_connect"))
    )
    (net (code "53") (name "unconnected-(IC2-DISPLAY_ENABLE_OUT-Pad4)") (class "Default")
      (node (ref "IC2") (pin "4") (pinfunction "DISPLAY_ENABLE_OUT_4") (pintype "passive+no_connect"))
    )
    (net (code "54") (name "unconnected-(IC2-UNGATED_\"_C\"_SEGMENT_OUT-Pad14)") (class "Default")
      (node (ref "IC2") (pin "14") (pinfunction "UNGATED_\"_C\"_SEGMENT_OUT_14") (pintype "passive+no_connect"))
    )
    (net (code "55") (name "unconnected-(IC3-CARRY_OUT-Pad5)") (class "Default")
      (node (ref "IC3") (pin "5") (pinfunction "CARRY_OUT_5") (pintype "passive+no_connect"))
    )
    (net (code "56") (name "unconnected-(IC3-DISPLAY_ENABLE_OUT-Pad4)") (class "Default")
      (node (ref "IC3") (pin "4") (pinfunction "DISPLAY_ENABLE_OUT_4") (pintype "passive+no_connect"))
    )
    (net (code "57") (name "unconnected-(IC3-UNGATED_\"_C\"_SEGMENT_OUT-Pad14)") (class "Default")
      (node (ref "IC3") (pin "14") (pinfunction "UNGATED_\"_C\"_SEGMENT_OUT_14") (pintype "passive+no_connect"))
    )
    (net (code "58") (name "unconnected-(SW1-Pad1)") (class "Default")
      (node (ref "SW1") (pin "1") (pinfunction "1_1") (pintype "passive+no_connect"))
    )
  )
)
